# IMX6ULL_CORE_sch8.net
KiCad netlist of a schematic drawn in Altium Designer
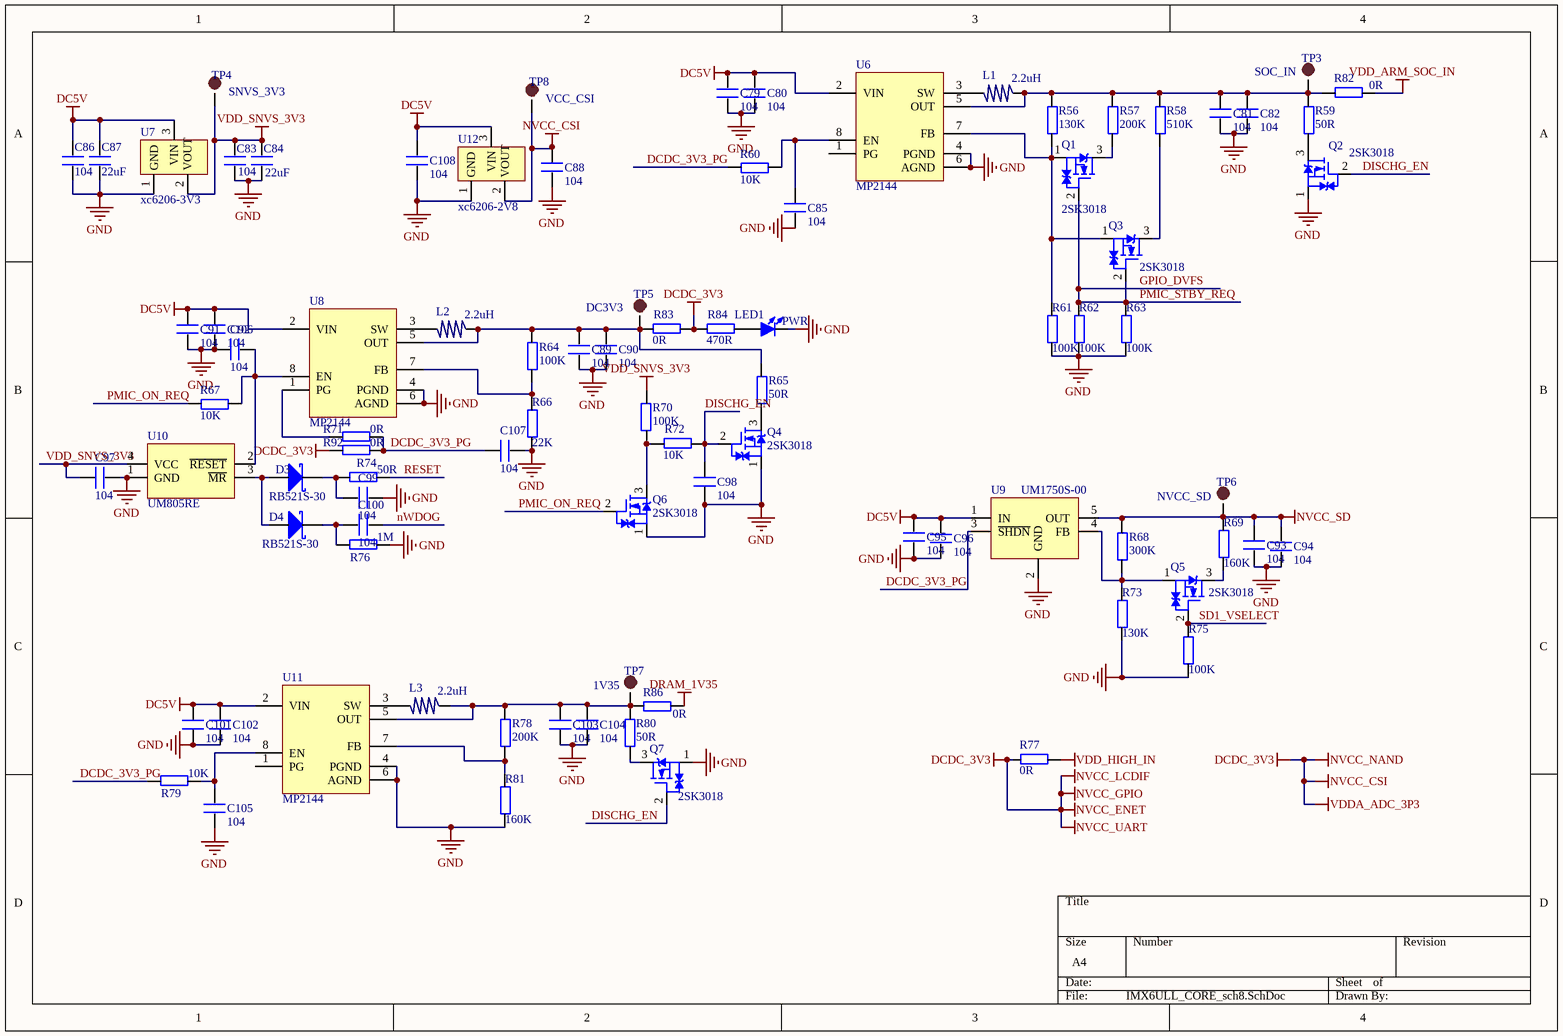
[diagram p0: IMX6ULL_CORE_sch8.SchDoc]

(export (version "E")
  (design (tool "Eeschema 10.0.6"))
  (components
    (comp (ref "C79") (value "104") (footprint "C 0402") (libsource (lib "linux_coreSCHLIB") (part "C")))
    (comp (ref "C80") (value "104") (footprint "C 0402") (libsource (lib "linux_coreSCHLIB") (part "C")))
    (comp (ref "C81") (value "104") (footprint "C 0402") (libsource (lib "linux_coreSCHLIB") (part "C")))
    (comp (ref "C82") (value "104") (footprint "C 0402") (libsource (lib "linux_coreSCHLIB") (part "C")))
    (comp (ref "C83") (value "104") (footprint "C 0402") (libsource (lib "linux_coreSCHLIB") (part "C")))
    (comp (ref "C84") (value "22uF") (footprint "C 0805") (libsource (lib "linux_coreSCHLIB") (part "C")))
    (comp (ref "C85") (value "104") (footprint "C 0402") (libsource (lib "linux_coreSCHLIB") (part "C")))
    (comp (ref "C86") (value "104") (footprint "C 0402") (libsource (lib "linux_coreSCHLIB") (part "C")))
    (comp (ref "C87") (value "22uF") (footprint "C 0805") (libsource (lib "linux_coreSCHLIB") (part "C")))
    (comp (ref "C88") (value "104") (footprint "C 0402") (libsource (lib "linux_coreSCHLIB") (part "C")))
    (comp (ref "C89") (value "104") (footprint "C 0402") (libsource (lib "linux_coreSCHLIB") (part "C")))
    (comp (ref "C90") (value "104") (footprint "C 0402") (libsource (lib "linux_coreSCHLIB") (part "C")))
    (comp (ref "C91") (value "104") (footprint "C 0402") (libsource (lib "linux_coreSCHLIB") (part "C")))
    (comp (ref "C92") (value "104") (footprint "C 0402") (libsource (lib "linux_coreSCHLIB") (part "C")))
    (comp (ref "C93") (value "104") (footprint "C 0402") (libsource (lib "linux_coreSCHLIB") (part "C")))
    (comp (ref "C94") (value "104") (footprint "C 0402") (libsource (lib "linux_coreSCHLIB") (part "C")))
    (comp (ref "C95") (value "104") (footprint "C 0402") (libsource (lib "linux_coreSCHLIB") (part "C")))
    (comp (ref "C96") (value "104") (footprint "C 0402") (libsource (lib "linux_coreSCHLIB") (part "C")))
    (comp (ref "C97") (value "104") (footprint "C 0402") (libsource (lib "linux_coreSCHLIB") (part "C")))
    (comp (ref "C98") (value "104") (footprint "C 0402") (libsource (lib "linux_coreSCHLIB") (part "C")))
    (comp (ref "C99") (value "104") (footprint "C 0402") (libsource (lib "linux_coreSCHLIB") (part "C")))
    (comp (ref "C100") (value "104") (footprint "C 0402") (libsource (lib "linux_coreSCHLIB") (part "C")))
    (comp (ref "C101") (value "104") (footprint "C 0402") (libsource (lib "linux_coreSCHLIB") (part "C")))
    (comp (ref "C102") (value "104") (footprint "C 0402") (libsource (lib "linux_coreSCHLIB") (part "C")))
    (comp (ref "C103") (value "104") (footprint "C 0402") (libsource (lib "linux_coreSCHLIB") (part "C")))
    (comp (ref "C104") (value "104") (footprint "C 0402") (libsource (lib "linux_coreSCHLIB") (part "C")))
    (comp (ref "C105") (value "104") (footprint "C 0402") (libsource (lib "linux_coreSCHLIB") (part "C")))
    (comp (ref "C106") (value "104") (footprint "C 0402") (libsource (lib "linux_coreSCHLIB") (part "C")))
    (comp (ref "C107") (value "104") (footprint "C 0402") (libsource (lib "linux_coreSCHLIB") (part "C")))
    (comp (ref "C108") (value "104") (footprint "C 0402") (libsource (lib "linux_coreSCHLIB") (part "C")))
    (comp (ref "D3")
      (value "RB521S-30")
      (footprint "SOD-523")
      (libsource (lib "linux_coreSCHLIB") (part "RB521S-30"))
    )
    (comp (ref "D4")
      (value "RB521S-30")
      (footprint "SOD-523")
      (libsource (lib "linux_coreSCHLIB") (part "RB521S-30"))
    )
    (comp (ref "L1") (value "2.2uH") (footprint "NR3015") (libsource (lib "linux_coreSCHLIB") (part "L")))
    (comp (ref "L2") (value "2.2uH") (footprint "NR3015") (libsource (lib "linux_coreSCHLIB") (part "L")))
    (comp (ref "L3") (value "2.2uH") (footprint "NR3015") (libsource (lib "linux_coreSCHLIB") (part "L")))
    (comp (ref "LED1")
      (value "PWR")
      (footprint "LED 0603B")
      (description "贴片LED")
      (fields (field (name "版权归属") "源创客"))
      (libsource (lib "linux_coreSCHLIB") (part "LED-SMD"))
    )
    (comp (ref "Q1")
      (value "2SK3018")
      (footprint "SC70-3L")
      (description "N沟场效应管  30V,0.1A")
      (fields (field (name "版权归属") "源创客"))
      (libsource (lib "linux_coreSCHLIB") (part "2SK3018"))
    )
    (comp (ref "Q2")
      (value "2SK3018")
      (footprint "SC70-3L")
      (description "N沟场效应管  30V,0.1A")
      (fields (field (name "版权归属") "源创客"))
      (libsource (lib "linux_coreSCHLIB") (part "2SK3018"))
    )
    (comp (ref "Q3")
      (value "2SK3018")
      (footprint "SC70-3L")
      (description "N沟场效应管  30V,0.1A")
      (fields (field (name "版权归属") "源创客"))
      (libsource (lib "linux_coreSCHLIB") (part "2SK3018"))
    )
    (comp (ref "Q4")
      (value "2SK3018")
      (footprint "SC70-3L")
      (description "N沟场效应管  30V,0.1A")
      (fields (field (name "版权归属") "源创客"))
      (libsource (lib "linux_coreSCHLIB") (part "2SK3018"))
    )
    (comp (ref "Q5")
      (value "2SK3018")
      (footprint "SC70-3L")
      (description "N沟场效应管  30V,0.1A")
      (fields (field (name "版权归属") "源创客"))
      (libsource (lib "linux_coreSCHLIB") (part "2SK3018"))
    )
    (comp (ref "Q6")
      (value "2SK3018")
      (footprint "SC70-3L")
      (description "N沟场效应管  30V,0.1A")
      (fields (field (name "版权归属") "源创客"))
      (libsource (lib "linux_coreSCHLIB") (part "2SK3018"))
    )
    (comp (ref "Q7")
      (value "2SK3018")
      (footprint "SC70-3L")
      (description "N沟场效应管  30V,0.1A")
      (fields (field (name "版权归属") "源创客"))
      (libsource (lib "linux_coreSCHLIB") (part "2SK3018"))
    )
    (comp (ref "R56") (value "130K") (footprint "R 0402") (libsource (lib "linux_coreSCHLIB") (part "R")))
    (comp (ref "R57") (value "200K") (footprint "R 0402") (libsource (lib "linux_coreSCHLIB") (part "R")))
    (comp (ref "R58") (value "510K") (footprint "R 0402") (libsource (lib "linux_coreSCHLIB") (part "R")))
    (comp (ref "R59") (value "50R") (footprint "R 0402") (libsource (lib "linux_coreSCHLIB") (part "R")))
    (comp (ref "R60") (value "10K") (footprint "R 0402") (libsource (lib "linux_coreSCHLIB") (part "R")))
    (comp (ref "R61") (value "100K") (footprint "R 0402") (libsource (lib "linux_coreSCHLIB") (part "R")))
    (comp (ref "R62") (value "100K") (footprint "R 0402") (libsource (lib "linux_coreSCHLIB") (part "R")))
    (comp (ref "R63") (value "100K") (footprint "R 0402") (libsource (lib "linux_coreSCHLIB") (part "R")))
    (comp (ref "R64") (value "100K") (footprint "R 0402") (libsource (lib "linux_coreSCHLIB") (part "R")))
    (comp (ref "R65") (value "50R") (footprint "R 0402") (libsource (lib "linux_coreSCHLIB") (part "R")))
    (comp (ref "R66") (value "22K") (footprint "R 0402") (libsource (lib "linux_coreSCHLIB") (part "R")))
    (comp (ref "R67") (value "10K") (footprint "R 0402") (libsource (lib "linux_coreSCHLIB") (part "R")))
    (comp (ref "R68") (value "300K") (footprint "R 0402") (libsource (lib "linux_coreSCHLIB") (part "R")))
    (comp (ref "R69") (value "160K") (footprint "R 0402") (libsource (lib "linux_coreSCHLIB") (part "R")))
    (comp (ref "R70") (value "100K") (footprint "R 0402") (libsource (lib "linux_coreSCHLIB") (part "R")))
    (comp (ref "R71") (value "0R") (footprint "R 0402") (libsource (lib "linux_coreSCHLIB") (part "R")))
    (comp (ref "R72") (value "10K") (footprint "R 0402") (libsource (lib "linux_coreSCHLIB") (part "R")))
    (comp (ref "R73") (value "130K") (footprint "R 0402") (libsource (lib "linux_coreSCHLIB") (part "R")))
    (comp (ref "R74") (value "50R") (footprint "R 0402") (libsource (lib "linux_coreSCHLIB") (part "R")))
    (comp (ref "R75") (value "100K") (footprint "R 0402") (libsource (lib "linux_coreSCHLIB") (part "R")))
    (comp (ref "R76") (value "1M") (footprint "R 0402") (libsource (lib "linux_coreSCHLIB") (part "R")))
    (comp (ref "R77") (value "0R") (footprint "R 0402") (libsource (lib "linux_coreSCHLIB") (part "R")))
    (comp (ref "R78") (value "200K") (footprint "R 0402") (libsource (lib "linux_coreSCHLIB") (part "R")))
    (comp (ref "R79") (value "10K") (footprint "R 0402") (libsource (lib "linux_coreSCHLIB") (part "R")))
    (comp (ref "R80") (value "50R") (footprint "R 0402") (libsource (lib "linux_coreSCHLIB") (part "R")))
    (comp (ref "R81") (value "160K") (footprint "R 0402") (libsource (lib "linux_coreSCHLIB") (part "R")))
    (comp (ref "R82") (value "0R") (footprint "R 0402") (libsource (lib "linux_coreSCHLIB") (part "R")))
    (comp (ref "R83") (value "0R") (footprint "R 0402") (libsource (lib "linux_coreSCHLIB") (part "R")))
    (comp (ref "R84") (value "470R") (footprint "R 0402") (libsource (lib "linux_coreSCHLIB") (part "R")))
    (comp (ref "R86") (value "0R") (footprint "R 0402") (libsource (lib "linux_coreSCHLIB") (part "R")))
    (comp (ref "R92") (value "0R") (footprint "R 0402") (libsource (lib "linux_coreSCHLIB") (part "R")))
    (comp (ref "TP3")
      (value "SOC_IN")
      (footprint "TP-1.0")
      (description "测试点")
      (libsource (lib "linux_coreSCHLIB") (part "TEST-POINT"))
    )
    (comp (ref "TP4")
      (value "SNVS_3V3")
      (footprint "TP-1.0")
      (description "测试点")
      (libsource (lib "linux_coreSCHLIB") (part "TEST-POINT"))
    )
    (comp (ref "TP5")
      (value "DC3V3")
      (footprint "TP-1.0")
      (description "测试点")
      (libsource (lib "linux_coreSCHLIB") (part "TEST-POINT"))
    )
    (comp (ref "TP6")
      (value "NVCC_SD")
      (footprint "TP-1.0")
      (description "测试点")
      (libsource (lib "linux_coreSCHLIB") (part "TEST-POINT"))
    )
    (comp (ref "TP7")
      (value "1V35")
      (footprint "TP-1.0")
      (description "测试点")
      (libsource (lib "linux_coreSCHLIB") (part "TEST-POINT"))
    )
    (comp (ref "TP8")
      (value "VCC_CSI")
      (footprint "TP-1.0")
      (description "测试点")
      (libsource (lib "linux_coreSCHLIB") (part "TEST-POINT"))
    )
    (comp (ref "U6")
      (value "MP2144")
      (footprint "SOT23-8L")
      (libsource (lib "linux_coreSCHLIB") (part "MP2144"))
    )
    (comp (ref "U7")
      (value "xc6206-3V3")
      (footprint "SOT23-3L")
      (libsource (lib "linux_coreSCHLIB") (part "xc6206-3V3"))
    )
    (comp (ref "U8")
      (value "MP2144")
      (footprint "SOT23-8L")
      (libsource (lib "linux_coreSCHLIB") (part "MP2144"))
    )
    (comp (ref "U9")
      (value "UM1750S-00")
      (footprint "SOT23-5L")
      (libsource (lib "linux_coreSCHLIB") (part "UM1750S-00"))
    )
    (comp (ref "U10")
      (value "UM805RE")
      (footprint "SOT143")
      (libsource (lib "linux_coreSCHLIB") (part "UM805RE"))
    )
    (comp (ref "U11")
      (value "MP2144")
      (footprint "SOT23-8L")
      (libsource (lib "linux_coreSCHLIB") (part "MP2159"))
    )
    (comp (ref "U12")
      (value "xc6206-2V8")
      (footprint "SOT23-3L")
      (libsource (lib "linux_coreSCHLIB") (part "xc6206-3V3"))
    )
  )
  (nets
    (net (code "1") (name "/DCDC_3V3_PG") (class "Default")
      (node (ref "C107") (pin "2") (pintype "passive"))
      (node (ref "R60") (pin "1") (pintype "passive"))
      (node (ref "R71") (pin "1") (pintype "passive"))
      (node (ref "R79") (pin "2") (pintype "passive"))
      (node (ref "R92") (pin "1") (pintype "passive"))
      (node (ref "U9") (pin "3") (pinfunction "~{SHDN}_3") (pintype "passive"))
    )
    (net (code "2") (name "/DISCHG_EN") (class "Default")
      (node (ref "C98") (pin "2") (pintype "passive"))
      (node (ref "Q2") (pin "2") (pinfunction "G_2") (pintype "passive"))
      (node (ref "Q4") (pin "2") (pinfunction "G_2") (pintype "passive"))
      (node (ref "Q7") (pin "2") (pinfunction "G_2") (pintype "passive"))
      (node (ref "R72") (pin "1") (pintype "passive"))
    )
    (net (code "3") (name "/GPIO_DVFS") (class "Default")
      (node (ref "Q1") (pin "2") (pinfunction "G_2") (pintype "passive"))
      (node (ref "Q3") (pin "2") (pinfunction "G_2") (pintype "passive"))
      (node (ref "R62") (pin "2") (pintype "passive"))
      (node (ref "R63") (pin "2") (pintype "passive"))
    )
    (net (code "4") (name "/PMIC_ON_REQ") (class "Default")
      (node (ref "Q6") (pin "2") (pinfunction "G_2") (pintype "passive"))
      (node (ref "R67") (pin "1") (pintype "passive"))
    )
    (net (code "5") (name "/RESET") (class "Default") (node (ref "R74") (pin "1") (pintype "passive")))
    (net (code "6") (name "/SD1_VSELECT") (class "Default")
      (node (ref "Q5") (pin "2") (pinfunction "G_2") (pintype "passive"))
      (node (ref "R75") (pin "2") (pintype "passive"))
    )
    (net (code "7") (name "/nWDOG") (class "Default") (node (ref "C100") (pin "1") (pintype "passive")))
    (net (code "8") (name "DC5V") (class "Default")
      (node (ref "C101") (pin "2") (pintype "passive"))
      (node (ref "C102") (pin "2") (pintype "passive"))
      (node (ref "C106") (pin "2") (pintype "passive"))
      (node (ref "C108") (pin "2") (pintype "passive"))
      (node (ref "C79") (pin "2") (pintype "passive"))
      (node (ref "C80") (pin "2") (pintype "passive"))
      (node (ref "C86") (pin "2") (pintype "passive"))
      (node (ref "C87") (pin "2") (pintype "passive"))
      (node (ref "C91") (pin "2") (pintype "passive"))
      (node (ref "C95") (pin "2") (pintype "passive"))
      (node (ref "C96") (pin "2") (pintype "passive"))
      (node (ref "U11") (pin "2") (pinfunction "VIN_2") (pintype "passive"))
      (node (ref "U12") (pin "3") (pinfunction "VIN_3") (pintype "passive"))
      (node (ref "U6") (pin "2") (pinfunction "VIN_2") (pintype "passive"))
      (node (ref "U7") (pin "3") (pinfunction "VIN_3") (pintype "passive"))
      (node (ref "U8") (pin "2") (pinfunction "VIN_2") (pintype "passive"))
      (node (ref "U9") (pin "1") (pinfunction "IN_1") (pintype "passive"))
    )
    (net (code "9") (name "DCDC_3V3") (class "Default")
      (node (ref "C88") (pin "2") (pintype "passive"))
      (node (ref "R77") (pin "2") (pintype "passive"))
      (node (ref "R83") (pin "1") (pintype "passive"))
      (node (ref "R84") (pin "2") (pintype "passive"))
      (node (ref "R92") (pin "2") (pintype "passive"))
      (node (ref "TP8") (pin "1") (pinfunction "1_1") (pintype "passive"))
      (node (ref "U12") (pin "2") (pinfunction "VOUT_2") (pintype "passive"))
    )
    (net (code "10") (name "DRAM_1V35") (class "Default") (node (ref "R86") (pin "2") (pintype "passive")))
    (net (code "11") (name "GND") (class "Default")
      (node (ref "C101") (pin "1") (pintype "passive"))
      (node (ref "C102") (pin "1") (pintype "passive"))
      (node (ref "C103") (pin "1") (pintype "passive"))
      (node (ref "C104") (pin "1") (pintype "passive"))
      (node (ref "C105") (pin "1") (pintype "passive"))
      (node (ref "C106") (pin "1") (pintype "passive"))
      (node (ref "C107") (pin "1") (pintype "passive"))
      (node (ref "C108") (pin "1") (pintype "passive"))
      (node (ref "C79") (pin "1") (pintype "passive"))
      (node (ref "C80") (pin "1") (pintype "passive"))
      (node (ref "C81") (pin "1") (pintype "passive"))
      (node (ref "C82") (pin "1") (pintype "passive"))
      (node (ref "C83") (pin "1") (pintype "passive"))
      (node (ref "C84") (pin "1") (pintype "passive"))
      (node (ref "C85") (pin "1") (pintype "passive"))
      (node (ref "C86") (pin "1") (pintype "passive"))
      (node (ref "C87") (pin "1") (pintype "passive"))
      (node (ref "C88") (pin "1") (pintype "passive"))
      (node (ref "C89") (pin "1") (pintype "passive"))
      (node (ref "C90") (pin "1") (pintype "passive"))
      (node (ref "C91") (pin "1") (pintype "passive"))
      (node (ref "C92") (pin "2") (pintype "passive"))
      (node (ref "C93") (pin "1") (pintype "passive"))
      (node (ref "C94") (pin "1") (pintype "passive"))
      (node (ref "C95") (pin "1") (pintype "passive"))
      (node (ref "C96") (pin "1") (pintype "passive"))
      (node (ref "C97") (pin "1") (pintype "passive"))
      (node (ref "C98") (pin "1") (pintype "passive"))
      (node (ref "C99") (pin "1") (pintype "passive"))
      (node (ref "LED1") (pin "2") (pinfunction "K_2") (pintype "passive"))
      (node (ref "Q2") (pin "1") (pinfunction "S_1") (pintype "passive"))
      (node (ref "Q4") (pin "1") (pinfunction "S_1") (pintype "passive"))
      (node (ref "Q6") (pin "1") (pinfunction "S_1") (pintype "passive"))
      (node (ref "Q7") (pin "1") (pinfunction "S_1") (pintype "passive"))
      (node (ref "R61") (pin "1") (pintype "passive"))
      (node (ref "R62") (pin "1") (pintype "passive"))
      (node (ref "R63") (pin "1") (pintype "passive"))
      (node (ref "R66") (pin "1") (pintype "passive"))
      (node (ref "R73") (pin "1") (pintype "passive"))
      (node (ref "R75") (pin "1") (pintype "passive"))
      (node (ref "R76") (pin "1") (pintype "passive"))
      (node (ref "R81") (pin "1") (pintype "passive"))
      (node (ref "U10") (pin "1") (pinfunction "GND_1") (pintype "passive"))
      (node (ref "U11") (pin "4") (pinfunction "PGND_4") (pintype "passive"))
      (node (ref "U11") (pin "6") (pinfunction "AGND_6") (pintype "passive"))
      (node (ref "U12") (pin "1") (pinfunction "GND_1") (pintype "passive"))
      (node (ref "U6") (pin "4") (pinfunction "PGND_4") (pintype "passive"))
      (node (ref "U6") (pin "6") (pinfunction "AGND_6") (pintype "passive"))
      (node (ref "U7") (pin "1") (pinfunction "GND_1") (pintype "passive"))
      (node (ref "U8") (pin "4") (pinfunction "PGND_4") (pintype "passive"))
      (node (ref "U8") (pin "6") (pinfunction "AGND_6") (pintype "passive"))
      (node (ref "U9") (pin "2") (pinfunction "GND_2") (pintype "passive"))
    )
    (net (code "12") (name "NVCC_SD") (class "Default")
      (node (ref "C93") (pin "2") (pintype "passive"))
      (node (ref "C94") (pin "2") (pintype "passive"))
      (node (ref "R68") (pin "2") (pintype "passive"))
      (node (ref "R69") (pin "2") (pintype "passive"))
      (node (ref "TP6") (pin "1") (pinfunction "1_1") (pintype "passive"))
      (node (ref "U9") (pin "5") (pinfunction "OUT_5") (pintype "passive"))
    )
    (net (code "13") (name "Net-(D3-A)") (class "Default")
      (node (ref "D3") (pin "1") (pinfunction "A_1") (pintype "passive"))
      (node (ref "D4") (pin "1") (pinfunction "A_1") (pintype "passive"))
      (node (ref "U10") (pin "3") (pinfunction "~{MR}_3") (pintype "passive"))
    )
    (net (code "14") (name "Net-(D3-C)") (class "Default")
      (node (ref "C99") (pin "2") (pintype "passive"))
      (node (ref "D3") (pin "2") (pinfunction "C_2") (pintype "passive"))
      (node (ref "R74") (pin "2") (pintype "passive"))
    )
    (net (code "15") (name "Net-(D4-C)") (class "Default")
      (node (ref "C100") (pin "2") (pintype "passive"))
      (node (ref "D4") (pin "2") (pinfunction "C_2") (pintype "passive"))
      (node (ref "R76") (pin "2") (pintype "passive"))
    )
    (net (code "16") (name "Net-(LED1-A)") (class "Default")
      (node (ref "LED1") (pin "1") (pinfunction "A_1") (pintype "passive"))
      (node (ref "R84") (pin "1") (pintype "passive"))
    )
    (net (code "17") (name "Net-(Q1-D)") (class "Default")
      (node (ref "Q1") (pin "3") (pinfunction "D_3") (pintype "passive"))
      (node (ref "R57") (pin "1") (pintype "passive"))
    )
    (net (code "18") (name "Net-(Q1-S)") (class "Default")
      (node (ref "Q1") (pin "1") (pinfunction "S_1") (pintype "passive"))
      (node (ref "Q3") (pin "1") (pinfunction "S_1") (pintype "passive"))
      (node (ref "R56") (pin "1") (pintype "passive"))
      (node (ref "R61") (pin "2") (pintype "passive"))
      (node (ref "U6") (pin "7") (pinfunction "FB_7") (pintype "passive"))
    )
    (net (code "19") (name "Net-(Q2-D)") (class "Default")
      (node (ref "Q2") (pin "3") (pinfunction "D_3") (pintype "passive"))
      (node (ref "R59") (pin "1") (pintype "passive"))
    )
    (net (code "20") (name "Net-(Q3-D)") (class "Default")
      (node (ref "Q3") (pin "3") (pinfunction "D_3") (pintype "passive"))
      (node (ref "R58") (pin "1") (pintype "passive"))
    )
    (net (code "21") (name "Net-(Q4-D)") (class "Default")
      (node (ref "Q4") (pin "3") (pinfunction "D_3") (pintype "passive"))
      (node (ref "R65") (pin "1") (pintype "passive"))
    )
    (net (code "22") (name "Net-(Q5-D)") (class "Default")
      (node (ref "Q5") (pin "3") (pinfunction "D_3") (pintype "passive"))
      (node (ref "R69") (pin "1") (pintype "passive"))
    )
    (net (code "23") (name "Net-(Q5-S)") (class "Default")
      (node (ref "Q5") (pin "1") (pinfunction "S_1") (pintype "passive"))
      (node (ref "R68") (pin "1") (pintype "passive"))
      (node (ref "R73") (pin "2") (pintype "passive"))
      (node (ref "U9") (pin "4") (pinfunction "FB_4") (pintype "passive"))
    )
    (net (code "24") (name "Net-(Q6-D)") (class "Default")
      (node (ref "Q6") (pin "3") (pinfunction "D_3") (pintype "passive"))
      (node (ref "R70") (pin "2") (pintype "passive"))
      (node (ref "R72") (pin "2") (pintype "passive"))
    )
    (net (code "25") (name "Net-(Q7-D)") (class "Default")
      (node (ref "Q7") (pin "3") (pinfunction "D_3") (pintype "passive"))
      (node (ref "R80") (pin "2") (pintype "passive"))
    )
    (net (code "26") (name "Net-(U6-EN)") (class "Default")
      (node (ref "C85") (pin "2") (pintype "passive"))
      (node (ref "R60") (pin "2") (pintype "passive"))
      (node (ref "U6") (pin "8") (pinfunction "EN_8") (pintype "passive"))
    )
    (net (code "27") (name "Net-(U6-OUT)") (class "Default")
      (node (ref "C81") (pin "2") (pintype "passive"))
      (node (ref "C82") (pin "2") (pintype "passive"))
      (node (ref "L1") (pin "1") (pintype "passive"))
      (node (ref "R56") (pin "2") (pintype "passive"))
      (node (ref "R57") (pin "2") (pintype "passive"))
      (node (ref "R58") (pin "2") (pintype "passive"))
      (node (ref "R59") (pin "2") (pintype "passive"))
      (node (ref "R82") (pin "2") (pintype "passive"))
      (node (ref "TP3") (pin "1") (pinfunction "1_1") (pintype "passive"))
      (node (ref "U6") (pin "5") (pinfunction "OUT_5") (pintype "passive"))
    )
    (net (code "28") (name "Net-(U6-SW)") (class "Default")
      (node (ref "L1") (pin "2") (pintype "passive"))
      (node (ref "U6") (pin "3") (pinfunction "SW_3") (pintype "passive"))
    )
    (net (code "29") (name "Net-(U8-FB)") (class "Default")
      (node (ref "R64") (pin "1") (pintype "passive"))
      (node (ref "R66") (pin "2") (pintype "passive"))
      (node (ref "U8") (pin "7") (pinfunction "FB_7") (pintype "passive"))
    )
    (net (code "30") (name "Net-(U8-OUT)") (class "Default")
      (node (ref "C89") (pin "2") (pintype "passive"))
      (node (ref "C90") (pin "2") (pintype "passive"))
      (node (ref "L2") (pin "1") (pintype "passive"))
      (node (ref "R64") (pin "2") (pintype "passive"))
      (node (ref "R65") (pin "2") (pintype "passive"))
      (node (ref "R83") (pin "2") (pintype "passive"))
      (node (ref "TP5") (pin "1") (pinfunction "1_1") (pintype "passive"))
      (node (ref "U8") (pin "5") (pinfunction "OUT_5") (pintype "passive"))
    )
    (net (code "31") (name "Net-(U8-PG)") (class "Default")
      (node (ref "R71") (pin "2") (pintype "passive"))
      (node (ref "U8") (pin "1") (pinfunction "PG_1") (pintype "passive"))
    )
    (net (code "32") (name "Net-(U8-SW)") (class "Default")
      (node (ref "L2") (pin "2") (pintype "passive"))
      (node (ref "U8") (pin "3") (pinfunction "SW_3") (pintype "passive"))
    )
    (net (code "33") (name "Net-(U10-~{RESET})") (class "Default")
      (node (ref "C92") (pin "1") (pintype "passive"))
      (node (ref "R67") (pin "2") (pintype "passive"))
      (node (ref "U10") (pin "2") (pinfunction "~{RESET}_2") (pintype "passive"))
      (node (ref "U8") (pin "8") (pinfunction "EN_8") (pintype "passive"))
    )
    (net (code "34") (name "Net-(U11-EN)") (class "Default")
      (node (ref "C105") (pin "2") (pintype "passive"))
      (node (ref "R79") (pin "1") (pintype "passive"))
      (node (ref "U11") (pin "8") (pinfunction "EN_8") (pintype "passive"))
    )
    (net (code "35") (name "Net-(U11-FB)") (class "Default")
      (node (ref "R78") (pin "1") (pintype "passive"))
      (node (ref "R81") (pin "2") (pintype "passive"))
      (node (ref "U11") (pin "7") (pinfunction "FB_7") (pintype "passive"))
    )
    (net (code "36") (name "Net-(U11-OUT)") (class "Default")
      (node (ref "C103") (pin "2") (pintype "passive"))
      (node (ref "C104") (pin "2") (pintype "passive"))
      (node (ref "L3") (pin "1") (pintype "passive"))
      (node (ref "R78") (pin "2") (pintype "passive"))
      (node (ref "R80") (pin "1") (pintype "passive"))
      (node (ref "R86") (pin "1") (pintype "passive"))
      (node (ref "TP7") (pin "1") (pinfunction "1_1") (pintype "passive"))
      (node (ref "U11") (pin "5") (pinfunction "OUT_5") (pintype "passive"))
    )
    (net (code "37") (name "Net-(U11-SW)") (class "Default")
      (node (ref "L3") (pin "2") (pintype "passive"))
      (node (ref "U11") (pin "3") (pinfunction "SW_3") (pintype "passive"))
    )
    (net (code "38") (name "VDD_ARM_SOC_IN") (class "Default")
      (node (ref "R82") (pin "1") (pintype "passive"))
    )
    (net (code "39") (name "VDD_HIGH_IN") (class "Default") (node (ref "R77") (pin "1") (pintype "passive")))
    (net (code "40") (name "VDD_SNVS_3V3") (class "Default")
      (node (ref "C83") (pin "2") (pintype "passive"))
      (node (ref "C84") (pin "2") (pintype "passive"))
      (node (ref "C97") (pin "2") (pintype "passive"))
      (node (ref "R70") (pin "1") (pintype "passive"))
      (node (ref "TP4") (pin "1") (pinfunction "1_1") (pintype "passive"))
      (node (ref "U10") (pin "4") (pinfunction "VCC_4") (pintype "passive"))
      (node (ref "U7") (pin "2") (pinfunction "VOUT_2") (pintype "passive"))
    )
    (net (code "41") (name "unconnected-(U6-PG-Pad1)") (class "Default")
      (node (ref "U6") (pin "1") (pinfunction "PG_1") (pintype "passive"))
    )
    (net (code "42") (name "unconnected-(U11-PG-Pad1)") (class "Default")
      (node (ref "U11") (pin "1") (pinfunction "PG_1") (pintype "passive"))
    )
  )
)
